# cc2652p.net
KiCad netlist of a schematic drawn in EAGLE
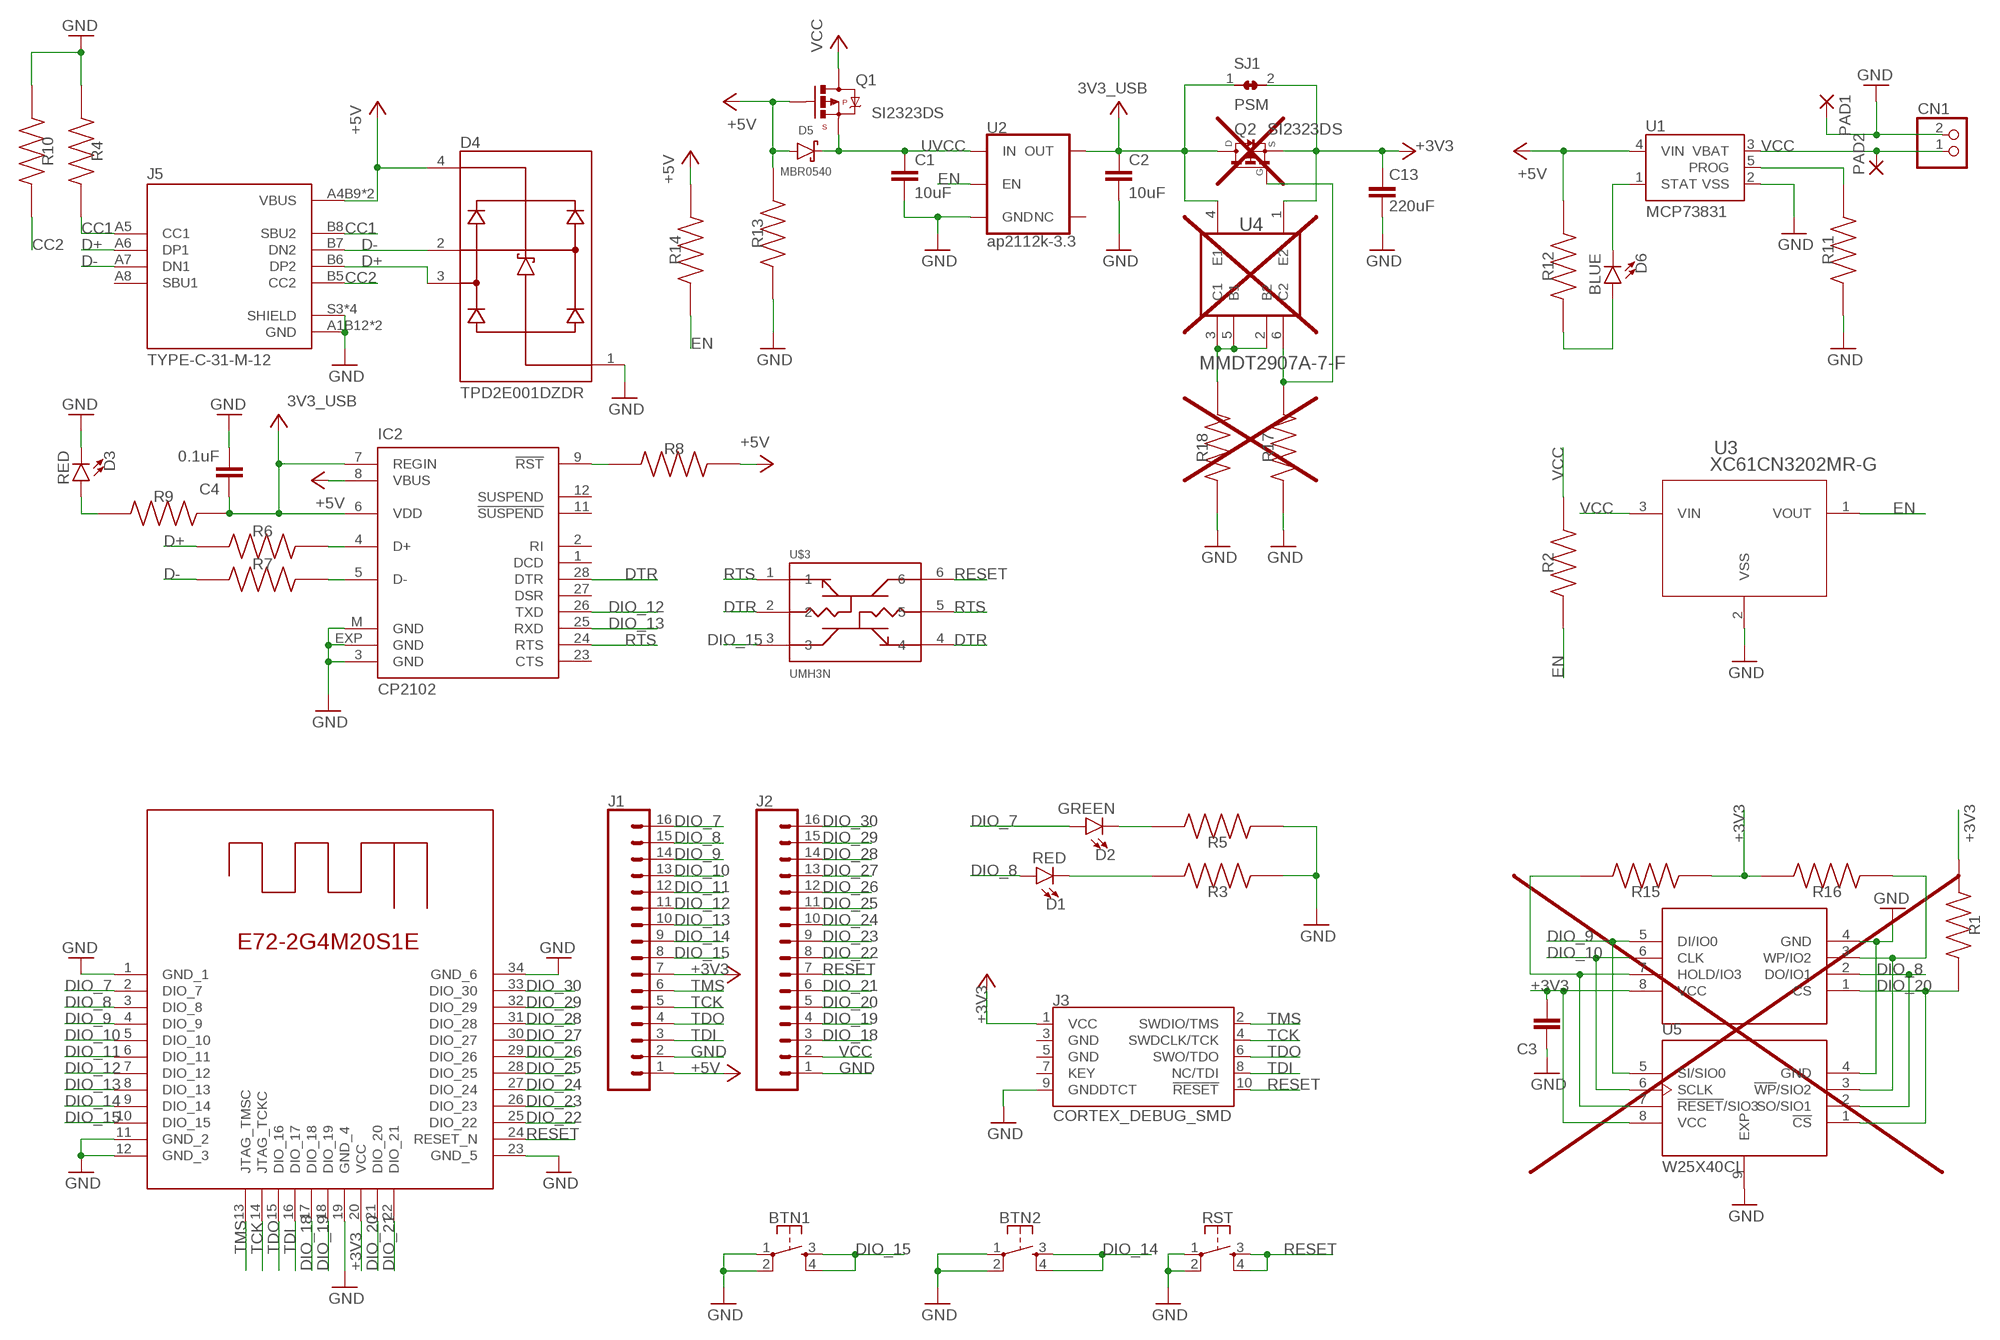
[diagram p0: schematic, sheet 1]

(export (version "E")
  (design (tool "Eeschema 10.0.6"))
  (components
    (comp (ref "BTN1")
      (value "MOMENTARY-SWITCH-SPST-2-SMD-4.6X2.8MM")
      (footprint "eagle-import:TACTILE_SWITCH_SMD_4.6X2.8MM")
      (libsource (lib "eagle-import") (part "MOMENTARY-SWITCH-SPST-2-SMD-4.6X2.8MM"))
    )
    (comp (ref "BTN2")
      (value "MOMENTARY-SWITCH-SPST-2-SMD-4.6X2.8MM")
      (footprint "eagle-import:TACTILE_SWITCH_SMD_4.6X2.8MM")
      (libsource (lib "eagle-import") (part "MOMENTARY-SWITCH-SPST-2-SMD-4.6X2.8MM"))
    )
    (comp (ref "C1")
      (value "10uF")
      (footprint "eagle-import:0603")
      (libsource (lib "eagle-import") (part "10UF-0603-6.3V-20%"))
    )
    (comp (ref "C2")
      (value "10uF")
      (footprint "eagle-import:0603")
      (libsource (lib "eagle-import") (part "10UF-0603-6.3V-20%"))
    )
    (comp (ref "C3")
      (value "100n")
      (footprint "eagle-import:CAPC1005X40N")
      (fields (field (name "MF") "Yageo") (field (name "MP") "RC0402FR-073M6L"))
      (libsource (lib "eagle-import") (part "CAP0402"))
    )
    (comp (ref "C4")
      (value "0.1uF")
      (footprint "eagle-import:0603")
      (libsource (lib "eagle-import") (part "0.1UF-0603-25V-(+80/-20%)"))
    )
    (comp (ref "C13")
      (value "220uF")
      (footprint "eagle-import:CAPM7343X310")
      (libsource (lib "eagle-import") (part "CTANTALUM-2917(7343-METRIC)_"))
    )
    (comp (ref "CN1")
      (value "JST_2PIN-SMT-RA")
      (footprint "eagle-import:JST-PH-2-SMT-RA")
      (libsource (lib "eagle-import") (part "JST_2PIN-SMT-RA"))
    )
    (comp (ref "D1")
      (value "RED")
      (footprint "eagle-import:LED-0603")
      (libsource (lib "eagle-import") (part "LED-RED0603"))
    )
    (comp (ref "D2")
      (value "GREEN")
      (footprint "eagle-import:LED-0603")
      (libsource (lib "eagle-import") (part "LED-GREEN0603"))
    )
    (comp (ref "D3")
      (value "RED")
      (footprint "eagle-import:LED-0603")
      (libsource (lib "eagle-import") (part "LED-RED0603"))
    )
    (comp (ref "D4")
      (value "TPD2E001DZDR")
      (footprint "eagle-import:SOT192P237X122-4N")
      (fields (field (name "MF") "Texas Instruments"))
      (libsource (lib "eagle-import") (part "TPD2E001DZDR"))
    )
    (comp (ref "D5")
      (value "MBR0540")
      (footprint "eagle-import:SOD-323")
      (libsource (lib "eagle-import") (part "DIODE-SCHOTTKY"))
    )
    (comp (ref "D6")
      (value "BLUE")
      (footprint "eagle-import:LED-0603")
      (libsource (lib "eagle-import") (part "LED-BLUE0603"))
    )
    (comp (ref "IC2")
      (value "CP2102")
      (footprint "eagle-import:MLP28")
      (fields (field (name "MF") "FARNELL") (field (name "MPN") "CP2102-GM"))
      (libsource (lib "eagle-import") (part "CP2102"))
    )
    (comp (ref "J1")
      (value "CONN_161X16_NO_SILK")
      (footprint "eagle-import:1X16_NO_SILK")
      (libsource (lib "eagle-import") (part "CONN_161X16_NO_SILK"))
    )
    (comp (ref "J2")
      (value "CONN_161X16_NO_SILK")
      (footprint "eagle-import:1X16_NO_SILK")
      (libsource (lib "eagle-import") (part "CONN_161X16_NO_SILK"))
    )
    (comp (ref "J3")
      (value "CORTEX_DEBUG_SMD")
      (footprint "eagle-import:SAMTECH_FTSH-105-01")
      (libsource (lib "eagle-import") (part "CORTEX_DEBUG_SMD"))
    )
    (comp (ref "J5")
      (value "TYPE-C-31-M-12")
      (footprint "eagle-import:HRO_TYPE-C-31-M-12")
      (fields (field (name "MF") "HRO Electronics Co., Ltd."))
      (libsource (lib "eagle-import") (part "TYPE-C-31-M-12"))
    )
    (comp (ref "PAD1")
      (value "WIREPADSMD1,27-254")
      (footprint "eagle-import:SMD1,27-2,54")
      (libsource (lib "eagle-import") (part "WIREPADSMD1,27-254"))
    )
    (comp (ref "PAD2")
      (value "WIREPADSMD1,27-254")
      (footprint "eagle-import:SMD1,27-2,54")
      (libsource (lib "eagle-import") (part "WIREPADSMD1,27-254"))
    )
    (comp (ref "Q1")
      (value "SI2323DS")
      (footprint "eagle-import:SOT23")
      (libsource (lib "eagle-import") (part "MOSFET-PCHANNEL"))
    )
    (comp (ref "Q2")
      (value "SI2323DS")
      (footprint "eagle-import:SOT23")
      (fields (field (name "MF") "Vishay Siliconix"))
      (libsource (lib "eagle-import") (part "SI2323DS"))
    )
    (comp (ref "R1")
      (value "100k")
      (footprint "eagle-import:RESC1005X40N")
      (fields (field (name "MF") "Yageo") (field (name "MP") "RC0402FR-073M6L"))
      (libsource (lib "eagle-import") (part "RC0402FR-073M6L"))
    )
    (comp (ref "R2")
      (value "10k")
      (footprint "eagle-import:RESC1005X40N")
      (fields (field (name "MF") "Yageo") (field (name "MP") "RC0402FR-073M6L"))
      (libsource (lib "eagle-import") (part "RC0402FR-073M6L"))
    )
    (comp (ref "R3")
      (value "2.2k")
      (footprint "eagle-import:RESC1005X40N")
      (fields (field (name "MF") "Yageo") (field (name "MP") "RC0402FR-073M6L"))
      (libsource (lib "eagle-import") (part "RC0402FR-073M6L"))
    )
    (comp (ref "R4")
      (value "5.1k")
      (footprint "eagle-import:RESC1005X40N")
      (fields (field (name "MF") "Yageo") (field (name "MP") "RC0402FR-073M6L"))
      (libsource (lib "eagle-import") (part "RC0402FR-073M6L"))
    )
    (comp (ref "R5")
      (value "2.2k")
      (footprint "eagle-import:RESC1005X40N")
      (fields (field (name "MF") "Yageo") (field (name "MP") "RC0402FR-073M6L"))
      (libsource (lib "eagle-import") (part "RC0402FR-073M6L"))
    )
    (comp (ref "R6")
      (value "33Ohm")
      (footprint "eagle-import:RESC1005X40N")
      (fields (field (name "MF") "Yageo") (field (name "MP") "RC0402FR-073M6L"))
      (libsource (lib "eagle-import") (part "RC0402FR-073M6L"))
    )
    (comp (ref "R7")
      (value "33Ohm")
      (footprint "eagle-import:RESC1005X40N")
      (fields (field (name "MF") "Yageo") (field (name "MP") "RC0402FR-073M6L"))
      (libsource (lib "eagle-import") (part "RC0402FR-073M6L"))
    )
    (comp (ref "R8")
      (value "4.7k")
      (footprint "eagle-import:RESC1005X40N")
      (fields (field (name "MF") "Yageo") (field (name "MP") "RC0402FR-073M6L"))
      (libsource (lib "eagle-import") (part "RC0402FR-073M6L"))
    )
    (comp (ref "R9")
      (value "2.2k")
      (footprint "eagle-import:RESC1005X40N")
      (fields (field (name "MF") "Yageo") (field (name "MP") "RC0402FR-073M6L"))
      (libsource (lib "eagle-import") (part "RC0402FR-073M6L"))
    )
    (comp (ref "R10")
      (value "5.1k")
      (footprint "eagle-import:RESC1005X40N")
      (fields (field (name "MF") "Yageo") (field (name "MP") "RC0402FR-073M6L"))
      (libsource (lib "eagle-import") (part "RC0402FR-073M6L"))
    )
    (comp (ref "R11")
      (value "2k")
      (footprint "eagle-import:RESC1005X40N")
      (fields (field (name "MF") "Yageo") (field (name "MP") "RC0402FR-073M6L"))
      (libsource (lib "eagle-import") (part "RC0402FR-073M6L"))
    )
    (comp (ref "R12")
      (value "2.2k")
      (footprint "eagle-import:RESC1005X40N")
      (fields (field (name "MF") "Yageo") (field (name "MP") "RC0402FR-073M6L"))
      (libsource (lib "eagle-import") (part "RC0402FR-073M6L"))
    )
    (comp (ref "R13")
      (value "100k")
      (footprint "eagle-import:RESC1005X40N")
      (fields (field (name "MF") "Yageo") (field (name "MP") "RC0402FR-073M6L"))
      (libsource (lib "eagle-import") (part "RC0402FR-073M6L"))
    )
    (comp (ref "R14")
      (value "10k")
      (footprint "eagle-import:RESC1005X40N")
      (fields (field (name "MF") "Yageo") (field (name "MP") "RC0402FR-073M6L"))
      (libsource (lib "eagle-import") (part "RC0402FR-073M6L"))
    )
    (comp (ref "R15")
      (value "10k")
      (footprint "eagle-import:RESC1005X40N")
      (fields (field (name "MF") "Yageo") (field (name "MP") "RC0402FR-073M6L"))
      (libsource (lib "eagle-import") (part "RC0402FR-073M6L"))
    )
    (comp (ref "R16")
      (value "10k")
      (footprint "eagle-import:RESC1005X40N")
      (fields (field (name "MF") "Yageo") (field (name "MP") "RC0402FR-073M6L"))
      (libsource (lib "eagle-import") (part "RC0402FR-073M6L"))
    )
    (comp (ref "R17")
      (value "100k")
      (footprint "eagle-import:RESC1005X40N")
      (fields (field (name "MF") "Yageo") (field (name "MP") "RC0402FR-073M6L"))
      (libsource (lib "eagle-import") (part "RC0402FR-073M6L"))
    )
    (comp (ref "R18")
      (value "100k")
      (footprint "eagle-import:RESC1005X40N")
      (fields (field (name "MF") "Yageo") (field (name "MP") "RC0402FR-073M6L"))
      (libsource (lib "eagle-import") (part "RC0402FR-073M6L"))
    )
    (comp (ref "RST")
      (value "MOMENTARY-SWITCH-SPST-2-SMD-4.6X2.8MM")
      (footprint "eagle-import:TACTILE_SWITCH_SMD_4.6X2.8MM")
      (libsource (lib "eagle-import") (part "MOMENTARY-SWITCH-SPST-2-SMD-4.6X2.8MM"))
    )
    (comp (ref "SJ1")
      (value "PSM")
      (footprint "eagle-import:SMALL_SOLDER_JUMPER_CLOSED")
      (libsource (lib "eagle-import") (part "SMALL_SOLDER_JUMPER_CLOSED"))
    )
    (comp (ref "U$1")
      (value "E72-2G4M20S1E")
      (footprint "eagle-import:E72-2G4M20S1E")
      (libsource (lib "eagle-import") (part "E72-2G4M20S1E"))
    )
    (comp (ref "U$2")
      (value "MX25R8035FM1IL0")
      (footprint "eagle-import:SO-8")
      (fields (field (name "MF") "Winbond Electronics") (field (name "MP") "W25Q80BVSNIG"))
      (libsource (lib "eagle-import") (part "W25Q80BVSNIG"))
    )
    (comp (ref "U$3")
      (value "UMH3N")
      (footprint "eagle-import:SOP65P210X100-6N")
      (fields (field (name "MF") "Rohm"))
      (libsource (lib "eagle-import") (part "UMH3N"))
    )
    (comp (ref "U1")
      (value "MCP73831")
      (footprint "eagle-import:SOT23-5")
      (libsource (lib "eagle-import") (part "MCP73831"))
    )
    (comp (ref "U2")
      (value "ap2112k-3.3")
      (footprint "eagle-import:SOT23-5")
      (libsource (lib "eagle-import") (part "V_REG_AP2112K-3.3V"))
    )
    (comp (ref "U3")
      (value "XC61CN3202MR-G")
      (footprint "eagle-import:XC61C_SOT-23_TOR")
      (libsource (lib "eagle-import") (part "XC61CN3202MR-G"))
    )
    (comp (ref "U4")
      (value "MMDT2907A-7-F")
      (footprint "eagle-import:SOT65P210X110-6N")
      (fields (field (name "MF") "Diodes Inc."))
      (libsource (lib "eagle-import") (part "MMDT2907A-7-F"))
    )
    (comp (ref "U5")
      (value "W25X40CL")
      (footprint "eagle-import:PSON50P200X300X60-9N")
      (fields (field (name "MF") "Macronix") (field (name "MP") "MX25R8035FZUIL0"))
      (libsource (lib "eagle-import") (part "MX25R8035FZUIL0"))
    )
  )
  (nets
    (net (code "1") (name "+3V3") (class "Default")
      (node (ref "C13") (pin "1") (pinfunction "1_1") (pintype "passive"))
      (node (ref "C3") (pin "2") (pinfunction "2_2") (pintype "passive"))
      (node (ref "J1") (pin "7") (pinfunction "7_7") (pintype "passive"))
      (node (ref "J3") (pin "1") (pinfunction "VCC_1") (pintype "bidirectional"))
      (node (ref "Q2") (pin "2") (pinfunction "S_2") (pintype "passive"))
      (node (ref "R1") (pin "1") (pinfunction "1_1") (pintype "passive"))
      (node (ref "R15") (pin "1") (pinfunction "1_1") (pintype "passive"))
      (node (ref "R16") (pin "2") (pinfunction "2_2") (pintype "passive"))
      (node (ref "SJ1") (pin "2") (pinfunction "2_2") (pintype "bidirectional"))
      (node (ref "U$1") (pin "20") (pinfunction "VCC_20") (pintype "bidirectional"))
      (node (ref "U$2") (pin "8") (pinfunction "VCC_8") (pintype "bidirectional"))
      (node (ref "U4") (pin "1") (pinfunction "E2_1") (pintype "passive"))
      (node (ref "U5") (pin "8") (pinfunction "VCC_8") (pintype "power_in"))
    )
    (net (code "2") (name "+5V") (class "Default")
      (node (ref "D4") (pin "4") (pinfunction "VCC_4") (pintype "power_in"))
      (node (ref "D5") (pin "A") (pinfunction "A_A") (pintype "passive"))
      (node (ref "IC2") (pin "8") (pinfunction "VBUS_8") (pintype "input"))
      (node (ref "J1") (pin "1") (pinfunction "1_1") (pintype "passive"))
      (node (ref "J5") (pin "A4B9") (pinfunction "VBUS_A4B9") (pintype "power_in"))
      (node (ref "J5") (pin "B4A9") (pinfunction "VBUS_B4A9") (pintype "power_in"))
      (node (ref "Q1") (pin "1") (pinfunction "G_1") (pintype "passive"))
      (node (ref "R12") (pin "2") (pinfunction "2_2") (pintype "passive"))
      (node (ref "R13") (pin "2") (pinfunction "2_2") (pintype "passive"))
      (node (ref "R14") (pin "2") (pinfunction "2_2") (pintype "passive"))
      (node (ref "R8") (pin "2") (pinfunction "2_2") (pintype "passive"))
      (node (ref "U1") (pin "4") (pinfunction "VIN_4") (pintype "power_in"))
    )
    (net (code "3") (name "/CC1") (class "Default")
      (node (ref "J5") (pin "A5") (pinfunction "CC1_A5") (pintype "bidirectional"))
      (node (ref "J5") (pin "B8") (pinfunction "SBU2_B8") (pintype "bidirectional"))
      (node (ref "R4") (pin "2") (pinfunction "2_2") (pintype "passive"))
    )
    (net (code "4") (name "/CC2") (class "Default")
      (node (ref "J5") (pin "B5") (pinfunction "CC2_B5") (pintype "bidirectional"))
      (node (ref "R10") (pin "2") (pinfunction "2_2") (pintype "passive"))
    )
    (net (code "5") (name "/D+") (class "Default")
      (node (ref "D4") (pin "3") (pinfunction "IO2_3") (pintype "bidirectional"))
      (node (ref "J5") (pin "A6") (pinfunction "DP1_A6") (pintype "bidirectional"))
      (node (ref "J5") (pin "B6") (pinfunction "DP2_B6") (pintype "bidirectional"))
      (node (ref "R6") (pin "1") (pinfunction "1_1") (pintype "passive"))
    )
    (net (code "6") (name "/D-") (class "Default")
      (node (ref "D4") (pin "2") (pinfunction "IO1_2") (pintype "bidirectional"))
      (node (ref "J5") (pin "A7") (pinfunction "DN1_A7") (pintype "bidirectional"))
      (node (ref "J5") (pin "B7") (pinfunction "DN2_B7") (pintype "bidirectional"))
      (node (ref "R7") (pin "1") (pinfunction "1_1") (pintype "passive"))
    )
    (net (code "7") (name "/DIO_7") (class "Default")
      (node (ref "D2") (pin "A") (pinfunction "A_A") (pintype "passive"))
      (node (ref "J1") (pin "16") (pinfunction "16_16") (pintype "passive"))
      (node (ref "U$1") (pin "2") (pinfunction "DIO_7_2") (pintype "bidirectional"))
    )
    (net (code "8") (name "/DIO_8") (class "Default")
      (node (ref "D1") (pin "A") (pinfunction "A_A") (pintype "passive"))
      (node (ref "J1") (pin "15") (pinfunction "15_15") (pintype "passive"))
      (node (ref "U$1") (pin "3") (pinfunction "DIO_8_3") (pintype "bidirectional"))
      (node (ref "U$2") (pin "2") (pinfunction "DO/IO1_2") (pintype "bidirectional"))
      (node (ref "U5") (pin "2") (pinfunction "SO/SIO1_2") (pintype "bidirectional"))
    )
    (net (code "9") (name "/DIO_9") (class "Default")
      (node (ref "J1") (pin "14") (pinfunction "14_14") (pintype "passive"))
      (node (ref "U$1") (pin "4") (pinfunction "DIO_9_4") (pintype "bidirectional"))
      (node (ref "U$2") (pin "5") (pinfunction "DI/IO0_5") (pintype "bidirectional"))
      (node (ref "U5") (pin "5") (pinfunction "SI/SIO0_5") (pintype "bidirectional"))
    )
    (net (code "10") (name "/DIO_10") (class "Default")
      (node (ref "J1") (pin "13") (pinfunction "13_13") (pintype "passive"))
      (node (ref "U$1") (pin "5") (pinfunction "DIO_10_5") (pintype "bidirectional"))
      (node (ref "U$2") (pin "6") (pinfunction "CLK_6") (pintype "bidirectional"))
      (node (ref "U5") (pin "6") (pinfunction "SCLK_6") (pintype "input"))
    )
    (net (code "11") (name "/DIO_11") (class "Default")
      (node (ref "J1") (pin "12") (pinfunction "12_12") (pintype "passive"))
      (node (ref "U$1") (pin "6") (pinfunction "DIO_11_6") (pintype "bidirectional"))
    )
    (net (code "12") (name "/DIO_12") (class "Default")
      (node (ref "IC2") (pin "26") (pinfunction "TXD_26") (pintype "output"))
      (node (ref "J1") (pin "11") (pinfunction "11_11") (pintype "passive"))
      (node (ref "U$1") (pin "7") (pinfunction "DIO_12_7") (pintype "bidirectional"))
    )
    (net (code "13") (name "/DIO_13") (class "Default")
      (node (ref "IC2") (pin "25") (pinfunction "RXD_25") (pintype "input"))
      (node (ref "J1") (pin "10") (pinfunction "10_10") (pintype "passive"))
      (node (ref "U$1") (pin "8") (pinfunction "DIO_13_8") (pintype "bidirectional"))
    )
    (net (code "14") (name "/DIO_14") (class "Default")
      (node (ref "BTN2") (pin "3") (pinfunction "3_3") (pintype "passive"))
      (node (ref "BTN2") (pin "4") (pinfunction "4_4") (pintype "passive"))
      (node (ref "J1") (pin "9") (pinfunction "9_9") (pintype "passive"))
      (node (ref "U$1") (pin "9") (pinfunction "DIO_14_9") (pintype "bidirectional"))
    )
    (net (code "15") (name "/DIO_15") (class "Default")
      (node (ref "BTN1") (pin "3") (pinfunction "3_3") (pintype "passive"))
      (node (ref "BTN1") (pin "4") (pinfunction "4_4") (pintype "passive"))
      (node (ref "J1") (pin "8") (pinfunction "8_8") (pintype "passive"))
      (node (ref "U$1") (pin "10") (pinfunction "DIO_15_10") (pintype "bidirectional"))
      (node (ref "U$3") (pin "3") (pinfunction "3_3") (pintype "bidirectional"))
    )
    (net (code "16") (name "/DIO_18") (class "Default")
      (node (ref "J2") (pin "3") (pinfunction "3_3") (pintype "passive"))
      (node (ref "U$1") (pin "17") (pinfunction "DIO_18_17") (pintype "bidirectional"))
    )
    (net (code "17") (name "/DIO_19") (class "Default")
      (node (ref "J2") (pin "4") (pinfunction "4_4") (pintype "passive"))
      (node (ref "U$1") (pin "18") (pinfunction "DIO_19_18") (pintype "bidirectional"))
    )
    (net (code "18") (name "/DIO_20") (class "Default")
      (node (ref "J2") (pin "5") (pinfunction "5_5") (pintype "passive"))
      (node (ref "R1") (pin "2") (pinfunction "2_2") (pintype "passive"))
      (node (ref "U$1") (pin "21") (pinfunction "DIO_20_21") (pintype "bidirectional"))
      (node (ref "U$2") (pin "1") (pinfunction "CS_1") (pintype "bidirectional"))
      (node (ref "U5") (pin "1") (pinfunction "~{CS}_1") (pintype "input"))
    )
    (net (code "19") (name "/DIO_21") (class "Default")
      (node (ref "J2") (pin "6") (pinfunction "6_6") (pintype "passive"))
      (node (ref "U$1") (pin "22") (pinfunction "DIO_21_22") (pintype "bidirectional"))
    )
    (net (code "20") (name "/DIO_22") (class "Default")
      (node (ref "J2") (pin "8") (pinfunction "8_8") (pintype "passive"))
      (node (ref "U$1") (pin "25") (pinfunction "DIO_22_25") (pintype "bidirectional"))
    )
    (net (code "21") (name "/DIO_23") (class "Default")
      (node (ref "J2") (pin "9") (pinfunction "9_9") (pintype "passive"))
      (node (ref "U$1") (pin "26") (pinfunction "DIO_23_26") (pintype "bidirectional"))
    )
    (net (code "22") (name "/DIO_24") (class "Default")
      (node (ref "J2") (pin "10") (pinfunction "10_10") (pintype "passive"))
      (node (ref "U$1") (pin "27") (pinfunction "DIO_24_27") (pintype "bidirectional"))
    )
    (net (code "23") (name "/DIO_25") (class "Default")
      (node (ref "J2") (pin "11") (pinfunction "11_11") (pintype "passive"))
      (node (ref "U$1") (pin "28") (pinfunction "DIO_25_28") (pintype "bidirectional"))
    )
    (net (code "24") (name "/DIO_26") (class "Default")
      (node (ref "J2") (pin "12") (pinfunction "12_12") (pintype "passive"))
      (node (ref "U$1") (pin "29") (pinfunction "DIO_26_29") (pintype "bidirectional"))
    )
    (net (code "25") (name "/DIO_27") (class "Default")
      (node (ref "J2") (pin "13") (pinfunction "13_13") (pintype "passive"))
      (node (ref "U$1") (pin "30") (pinfunction "DIO_27_30") (pintype "bidirectional"))
    )
    (net (code "26") (name "/DIO_28") (class "Default")
      (node (ref "J2") (pin "14") (pinfunction "14_14") (pintype "passive"))
      (node (ref "U$1") (pin "31") (pinfunction "DIO_28_31") (pintype "bidirectional"))
    )
    (net (code "27") (name "/DIO_29") (class "Default")
      (node (ref "J2") (pin "15") (pinfunction "15_15") (pintype "passive"))
      (node (ref "U$1") (pin "32") (pinfunction "DIO_29_32") (pintype "bidirectional"))
    )
    (net (code "28") (name "/DIO_30") (class "Default")
      (node (ref "J2") (pin "16") (pinfunction "16_16") (pintype "passive"))
      (node (ref "U$1") (pin "33") (pinfunction "DIO_30_33") (pintype "bidirectional"))
    )
    (net (code "29") (name "/DTR") (class "Default")
      (node (ref "IC2") (pin "28") (pinfunction "DTR_28") (pintype "output"))
      (node (ref "U$3") (pin "2") (pinfunction "2_2") (pintype "bidirectional"))
      (node (ref "U$3") (pin "4") (pinfunction "4_4") (pintype "bidirectional"))
    )
    (net (code "30") (name "/EN") (class "Default")
      (node (ref "R14") (pin "1") (pinfunction "1_1") (pintype "passive"))
      (node (ref "R2") (pin "1") (pinfunction "1_1") (pintype "passive"))
      (node (ref "U2") (pin "3") (pinfunction "EN_3") (pintype "input"))
      (node (ref "U3") (pin "1") (pinfunction "VOUT_1") (pintype "output"))
    )
    (net (code "31") (name "/RESET") (class "Default")
      (node (ref "J2") (pin "7") (pinfunction "7_7") (pintype "passive"))
      (node (ref "J3") (pin "10") (pinfunction "~{RESET}_10") (pintype "bidirectional"))
      (node (ref "RST") (pin "3") (pinfunction "3_3") (pintype "passive"))
      (node (ref "RST") (pin "4") (pinfunction "4_4") (pintype "passive"))
      (node (ref "U$1") (pin "24") (pinfunction "RESET_N_24") (pintype "bidirectional"))
      (node (ref "U$3") (pin "6") (pinfunction "6_6") (pintype "bidirectional"))
    )
    (net (code "32") (name "/RTS") (class "Default")
      (node (ref "IC2") (pin "24") (pinfunction "RTS_24") (pintype "output"))
      (node (ref "U$3") (pin "1") (pinfunction "1_1") (pintype "bidirectional"))
      (node (ref "U$3") (pin "5") (pinfunction "5_5") (pintype "bidirectional"))
    )
    (net (code "33") (name "/TCK") (class "Default")
      (node (ref "J1") (pin "5") (pinfunction "5_5") (pintype "passive"))
      (node (ref "J3") (pin "4") (pinfunction "SWDCLK/TCK_4") (pintype "bidirectional"))
      (node (ref "U$1") (pin "14") (pinfunction "JTAG_TCKC_14") (pintype "bidirectional"))
    )
    (net (code "34") (name "/TDI") (class "Default")
      (node (ref "J1") (pin "3") (pinfunction "3_3") (pintype "passive"))
      (node (ref "J3") (pin "8") (pinfunction "NC/TDI_8") (pintype "bidirectional"))
      (node (ref "U$1") (pin "16") (pinfunction "DIO_17_16") (pintype "bidirectional"))
    )
    (net (code "35") (name "/TDO") (class "Default")
      (node (ref "J1") (pin "4") (pinfunction "4_4") (pintype "passive"))
      (node (ref "J3") (pin "6") (pinfunction "SWO/TDO_6") (pintype "bidirectional"))
      (node (ref "U$1") (pin "15") (pinfunction "DIO_16_15") (pintype "bidirectional"))
    )
    (net (code "36") (name "/TMS") (class "Default")
      (node (ref "J1") (pin "6") (pinfunction "6_6") (pintype "passive"))
      (node (ref "J3") (pin "2") (pinfunction "SWDIO/TMS_2") (pintype "bidirectional"))
      (node (ref "U$1") (pin "13") (pinfunction "JTAG_TMSC_13") (pintype "bidirectional"))
    )
    (net (code "37") (name "/UVCC") (class "Default")
      (node (ref "C1") (pin "1") (pinfunction "1_1") (pintype "passive"))
      (node (ref "D5") (pin "C") (pinfunction "C_C") (pintype "passive"))
      (node (ref "Q1") (pin "2") (pinfunction "S_2") (pintype "passive"))
      (node (ref "U2") (pin "1") (pinfunction "IN_1") (pintype "input"))
    )
    (net (code "38") (name "3V3_USB") (class "Default")
      (node (ref "C2") (pin "1") (pinfunction "1_1") (pintype "passive"))
      (node (ref "C4") (pin "1") (pinfunction "1_1") (pintype "passive"))
      (node (ref "IC2") (pin "6") (pinfunction "VDD_6") (pintype "power_in"))
      (node (ref "IC2") (pin "7") (pinfunction "REGIN_7") (pintype "passive"))
      (node (ref "Q2") (pin "3") (pinfunction "D_3") (pintype "passive"))
      (node (ref "R9") (pin "1") (pinfunction "1_1") (pintype "passive"))
      (node (ref "SJ1") (pin "1") (pinfunction "1_1") (pintype "bidirectional"))
      (node (ref "U2") (pin "5") (pinfunction "OUT_5") (pintype "passive"))
      (node (ref "U4") (pin "4") (pinfunction "E1_4") (pintype "passive"))
    )
    (net (code "39") (name "GND") (class "Default")
      (node (ref "BTN1") (pin "1") (pinfunction "1_1") (pintype "passive"))
      (node (ref "BTN1") (pin "2") (pinfunction "2_2") (pintype "passive"))
      (node (ref "BTN2") (pin "1") (pinfunction "1_1") (pintype "passive"))
      (node (ref "BTN2") (pin "2") (pinfunction "2_2") (pintype "passive"))
      (node (ref "C1") (pin "2") (pinfunction "2_2") (pintype "passive"))
      (node (ref "C13") (pin "2") (pinfunction "2_2") (pintype "passive"))
      (node (ref "C2") (pin "2") (pinfunction "2_2") (pintype "passive"))
      (node (ref "C3") (pin "1") (pinfunction "1_1") (pintype "passive"))
      (node (ref "C4") (pin "2") (pinfunction "2_2") (pintype "passive"))
      (node (ref "CN1") (pin "2") (pinfunction "1_2") (pintype "passive"))
      (node (ref "D3") (pin "C") (pinfunction "C_C") (pintype "passive"))
      (node (ref "D4") (pin "1") (pinfunction "GND_1") (pintype "power_in"))
      (node (ref "IC2") (pin "3") (pinfunction "GND_3") (pintype "power_in"))
      (node (ref "IC2") (pin "EXP") (pinfunction "GND_EXP") (pintype "power_in"))
      (node (ref "IC2") (pin "M") (pinfunction "GND_M") (pintype "power_in"))
      (node (ref "J1") (pin "2") (pinfunction "2_2") (pintype "passive"))
      (node (ref "J2") (pin "1") (pinfunction "1_1") (pintype "passive"))
      (node (ref "J3") (pin "9") (pinfunction "GNDDTCT_9") (pintype "bidirectional"))
      (node (ref "J5") (pin "A1B12") (pinfunction "GND_A1B12") (pintype "power_in"))
      (node (ref "J5") (pin "B1A12") (pinfunction "GND_B1A12") (pintype "power_in"))
      (node (ref "J5") (pin "S3") (pinfunction "SHIELD_S3") (pintype "passive"))
      (node (ref "J5") (pin "S4") (pinfunction "SHIELD_S4") (pintype "passive"))
      (node (ref "J5") (pin "S5") (pinfunction "SHIELD_S5") (pintype "passive"))
      (node (ref "J5") (pin "S6") (pinfunction "SHIELD_S6") (pintype "passive"))
      (node (ref "PAD1") (pin "1") (pinfunction "P_1") (pintype "passive"))
      (node (ref "R10") (pin "1") (pinfunction "1_1") (pintype "passive"))
      (node (ref "R11") (pin "1") (pinfunction "1_1") (pintype "passive"))
      (node (ref "R13") (pin "1") (pinfunction "1_1") (pintype "passive"))
      (node (ref "R17") (pin "1") (pinfunction "1_1") (pintype "passive"))
      (node (ref "R18") (pin "1") (pinfunction "1_1") (pintype "passive"))
      (node (ref "R3") (pin "1") (pinfunction "1_1") (pintype "passive"))
      (node (ref "R4") (pin "1") (pinfunction "1_1") (pintype "passive"))
      (node (ref "R5") (pin "1") (pinfunction "1_1") (pintype "passive"))
      (node (ref "RST") (pin "1") (pinfunction "1_1") (pintype "passive"))
      (node (ref "RST") (pin "2") (pinfunction "2_2") (pintype "passive"))
      (node (ref "U$1") (pin "1") (pinfunction "GND_1_1") (pintype "bidirectional"))
      (node (ref "U$1") (pin "11") (pinfunction "GND_2_11") (pintype "bidirectional"))
      (node (ref "U$1") (pin "12") (pinfunction "GND_3_12") (pintype "bidirectional"))
      (node (ref "U$1") (pin "19") (pinfunction "GND_4_19") (pintype "bidirectional"))
      (node (ref "U$1") (pin "23") (pinfunction "GND_5_23") (pintype "bidirectional"))
      (node (ref "U$1") (pin "34") (pinfunction "GND_6_34") (pintype "bidirectional"))
      (node (ref "U$2") (pin "4") (pinfunction "GND_4") (pintype "bidirectional"))
      (node (ref "U1") (pin "2") (pinfunction "VSS_2") (pintype "power_in"))
      (node (ref "U2") (pin "2") (pinfunction "GND_2") (pintype "input"))
      (node (ref "U3") (pin "2") (pinfunction "VSS_2") (pintype "passive"))
      (node (ref "U5") (pin "4") (pinfunction "GND_4") (pintype "power_in"))
      (node (ref "U5") (pin "9") (pinfunction "EXP_9") (pintype "power_in"))
    )
    (net (code "40") (name "Net-(D1-PadC)") (class "Default")
      (node (ref "D1") (pin "C") (pinfunction "C_C") (pintype "passive"))
      (node (ref "R3") (pin "2") (pinfunction "2_2") (pintype "passive"))
    )
    (net (code "41") (name "Net-(D2-PadC)") (class "Default")
      (node (ref "D2") (pin "C") (pinfunction "C_C") (pintype "passive"))
      (node (ref "R5") (pin "2") (pinfunction "2_2") (pintype "passive"))
    )
    (net (code "42") (name "Net-(D3-PadA)") (class "Default")
      (node (ref "D3") (pin "A") (pinfunction "A_A") (pintype "passive"))
      (node (ref "R9") (pin "2") (pinfunction "2_2") (pintype "passive"))
    )
    (net (code "43") (name "Net-(D6-PadA)") (class "Default")
      (node (ref "D6") (pin "A") (pinfunction "A_A") (pintype "passive"))
      (node (ref "R12") (pin "1") (pinfunction "1_1") (pintype "passive"))
    )
    (net (code "44") (name "Net-(IC2-D+)") (class "Default")
      (node (ref "IC2") (pin "4") (pinfunction "D+_4") (pintype "bidirectional"))
      (node (ref "R6") (pin "2") (pinfunction "2_2") (pintype "passive"))
    )
    (net (code "45") (name "Net-(IC2-D-)") (class "Default")
      (node (ref "IC2") (pin "5") (pinfunction "D-_5") (pintype "bidirectional"))
      (node (ref "R7") (pin "2") (pinfunction "2_2") (pintype "passive"))
    )
    (net (code "46") (name "Net-(IC2-~{RST})") (class "Default")
      (node (ref "IC2") (pin "9") (pinfunction "~{RST}_9") (pintype "bidirectional"))
      (node (ref "R8") (pin "1") (pinfunction "1_1") (pintype "passive"))
    )
    (net (code "47") (name "Net-(Q2-G)") (class "Default")
      (node (ref "Q2") (pin "1") (pinfunction "G_1") (pintype "passive"))
      (node (ref "R17") (pin "2") (pinfunction "2_2") (pintype "passive"))
      (node (ref "U4") (pin "6") (pinfunction "C2_6") (pintype "passive"))
    )
    (net (code "48") (name "Net-(U$2-HOLD{slash}IO3)") (class "Default")
      (node (ref "R15") (pin "2") (pinfunction "2_2") (pintype "passive"))
      (node (ref "U$2") (pin "7") (pinfunction "HOLD/IO3_7") (pintype "bidirectional"))
      (node (ref "U5") (pin "7") (pinfunction "~{RESET}/SIO3_7") (pintype "bidirectional"))
    )
    (net (code "49") (name "Net-(U$2-WP{slash}IO2)") (class "Default")
      (node (ref "R16") (pin "1") (pinfunction "1_1") (pintype "passive"))
      (node (ref "U$2") (pin "3") (pinfunction "WP/IO2_3") (pintype "bidirectional"))
      (node (ref "U5") (pin "3") (pinfunction "~{WP}/SIO2_3") (pintype "bidirectional"))
    )
    (net (code "50") (name "Net-(U1-PROG)") (class "Default")
      (node (ref "R11") (pin "2") (pinfunction "2_2") (pintype "passive"))
      (node (ref "U1") (pin "5") (pinfunction "PROG_5") (pintype "input"))
    )
    (net (code "51") (name "Net-(U1-STAT)") (class "Default")
      (node (ref "D6") (pin "C") (pinfunction "C_C") (pintype "passive"))
      (node (ref "U1") (pin "1") (pinfunction "STAT_1") (pintype "output"))
    )
    (net (code "52") (name "Net-(U4-B1)") (class "Default")
      (node (ref "R18") (pin "2") (pinfunction "2_2") (pintype "passive"))
      (node (ref "U4") (pin "2") (pinfunction "B2_2") (pintype "passive"))
      (node (ref "U4") (pin "3") (pinfunction "C1_3") (pintype "passive"))
      (node (ref "U4") (pin "5") (pinfunction "B1_5") (pintype "passive"))
    )
    (net (code "53") (name "VCC") (class "Default")
      (node (ref "CN1") (pin "1") (pinfunction "2_1") (pintype "passive"))
      (node (ref "J2") (pin "2") (pinfunction "2_2") (pintype "passive"))
      (node (ref "PAD2") (pin "1") (pinfunction "P_1") (pintype "passive"))
      (node (ref "Q1") (pin "3") (pinfunction "D_3") (pintype "passive"))
      (node (ref "R2") (pin "2") (pinfunction "2_2") (pintype "passive"))
      (node (ref "U1") (pin "3") (pinfunction "VBAT_3") (pintype "power_in"))
      (node (ref "U3") (pin "3") (pinfunction "VIN_3") (pintype "power_in"))
    )
    (net (code "54") (name "unconnected-(IC2-CTS-Pad23)") (class "Default")
      (node (ref "IC2") (pin "23") (pinfunction "CTS_23") (pintype "input"))
    )
    (net (code "55") (name "unconnected-(IC2-DCD-Pad1)") (class "Default")
      (node (ref "IC2") (pin "1") (pinfunction "DCD_1") (pintype "input"))
    )
    (net (code "56") (name "unconnected-(IC2-DSR-Pad27)") (class "Default")
      (node (ref "IC2") (pin "27") (pinfunction "DSR_27") (pintype "input"))
    )
    (net (code "57") (name "unconnected-(IC2-RI-Pad2)") (class "Default")
      (node (ref "IC2") (pin "2") (pinfunction "RI_2") (pintype "input"))
    )
    (net (code "58") (name "unconnected-(IC2-SUSPEND-Pad12)") (class "Default")
      (node (ref "IC2") (pin "12") (pinfunction "SUSPEND_12") (pintype "output"))
    )
    (net (code "59") (name "unconnected-(IC2-~{SUSPEND}-Pad11)") (class "Default")
      (node (ref "IC2") (pin "11") (pinfunction "~{SUSPEND}_11") (pintype "output"))
    )
    (net (code "60") (name "unconnected-(J3-GND-Pad3)") (class "Default")
      (node (ref "J3") (pin "3") (pinfunction "GND_3") (pintype "bidirectional"))
    )
    (net (code "61") (name "unconnected-(J3-GND-Pad5)") (class "Default")
      (node (ref "J3") (pin "5") (pinfunction "GND_5") (pintype "bidirectional"))
    )
    (net (code "62") (name "unconnected-(J3-KEY-Pad7)") (class "Default")
      (node (ref "J3") (pin "7") (pinfunction "KEY_7") (pintype "bidirectional"))
    )
    (net (code "63") (name "unconnected-(J5-SBU1-PadA8)") (class "Default")
      (node (ref "J5") (pin "A8") (pinfunction "SBU1_A8") (pintype "bidirectional"))
    )
    (net (code "64") (name "unconnected-(U2-NC-Pad4)") (class "Default")
      (node (ref "U2") (pin "4") (pinfunction "NC_4") (pintype "no_connect"))
    )
  )
)
